# jha_ssr.net
KiCad netlist of a schematic drawn in EAGLE
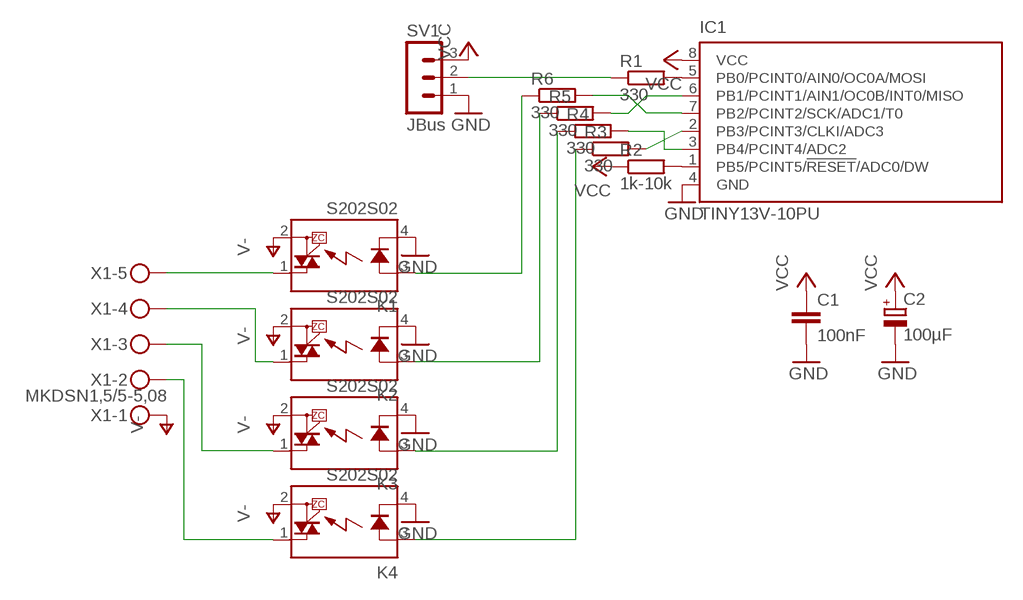
[diagram p0: schematic, sheet 1]

(export (version "E")
  (design (tool "Eeschema 10.0.6"))
  (components
    (comp (ref "C1")
      (value "100nF")
      (footprint "eagle-import:C0603")
      (libsource (lib "eagle-import") (part "C-EUC0603"))
    )
    (comp (ref "C2")
      (value "100µF")
      (footprint "eagle-import:E2,5-5")
      (libsource (lib "eagle-import") (part "CPOL-EUE2.5-5"))
    )
    (comp (ref "IC1")
      (value "TINY13V-10PU")
      (footprint "eagle-import:DIL08")
      (fields
        (field (name "MPN") "ATTINY13V-10PU")
        (field (name "MPN_1") "ATTINY13V-10PU")
        (field (name "OC_FARNELL") "9171576")
        (field (name "OC_NEWARK") "96K6523")
      )
      (libsource (lib "eagle-import") (part "TINY13PUV-10"))
    )
    (comp (ref "K1")
      (value "S202S02")
      (footprint "eagle-import:S202S02")
      (fields (field (name "MPN") "S202S02F"))
      (libsource (lib "eagle-import") (part "S02S022"))
    )
    (comp (ref "K2")
      (value "S202S02")
      (footprint "eagle-import:S202S02")
      (fields (field (name "MPN") "S202S02F"))
      (libsource (lib "eagle-import") (part "S02S022"))
    )
    (comp (ref "K3")
      (value "S202S02")
      (footprint "eagle-import:S202S02")
      (fields (field (name "MPN") "S202S02F"))
      (libsource (lib "eagle-import") (part "S02S022"))
    )
    (comp (ref "K4")
      (value "S202S02")
      (footprint "eagle-import:S202S02")
      (fields (field (name "MPN") "S202S02F"))
      (libsource (lib "eagle-import") (part "S02S022"))
    )
    (comp (ref "R1")
      (value "330")
      (footprint "eagle-import:R0805")
      (libsource (lib "eagle-import") (part "R-EU_R0805"))
    )
    (comp (ref "R2")
      (value "1k-10k")
      (footprint "eagle-import:R0805")
      (libsource (lib "eagle-import") (part "R-EU_R0805"))
    )
    (comp (ref "R3")
      (value "330")
      (footprint "eagle-import:R0805")
      (libsource (lib "eagle-import") (part "R-EU_R0805"))
    )
    (comp (ref "R4")
      (value "330")
      (footprint "eagle-import:R0805")
      (libsource (lib "eagle-import") (part "R-EU_R0805"))
    )
    (comp (ref "R5")
      (value "330")
      (footprint "eagle-import:R0805")
      (libsource (lib "eagle-import") (part "R-EU_R0805"))
    )
    (comp (ref "R6")
      (value "330")
      (footprint "eagle-import:R0805")
      (libsource (lib "eagle-import") (part "R-EU_R0805"))
    )
    (comp (ref "SV1")
      (value "JBus")
      (footprint "eagle-import:MA03-1")
      (libsource (lib "eagle-import") (part "MA03-1"))
    )
    (comp (ref "X1")
      (value "MKDSN1,5/5-5,08")
      (footprint "eagle-import:MKDSN1,5_5-5,08")
      (fields (field (name "MPN") "SMKDSN1,5/5-5,08"))
      (libsource (lib "eagle-import") (part "MKDSN1,5/5-5,08"))
    )
  )
  (nets
    (net (code "1") (name "GND") (class "Default")
      (node (ref "C1") (pin "2") (pinfunction "2_2") (pintype "passive"))
      (node (ref "C2") (pin "-") (pinfunction "-_-") (pintype "passive"))
      (node (ref "IC1") (pin "4") (pinfunction "GND_4") (pintype "power_in"))
      (node (ref "K1") (pin "4") (pinfunction "K_4") (pintype "passive"))
      (node (ref "K2") (pin "4") (pinfunction "K_4") (pintype "passive"))
      (node (ref "K3") (pin "4") (pinfunction "K_4") (pintype "passive"))
      (node (ref "K4") (pin "4") (pinfunction "K_4") (pintype "passive"))
      (node (ref "SV1") (pin "1") (pinfunction "1_1") (pintype "passive"))
    )
    (net (code "2") (name "Net-(IC1-PB0{slash}PCINT0{slash}AIN0{slash}OC0A{slash}MOSI)") (class "Default")
      (node (ref "IC1") (pin "5") (pinfunction "PB0/PCINT0/AIN0/OC0A/MOSI_5") (pintype "bidirectional"))
      (node (ref "R1") (pin "2") (pinfunction "2_2") (pintype "passive"))
    )
    (net (code "3") (name "Net-(IC1-PB1{slash}PCINT1{slash}AIN1{slash}OC0B{slash}INT0{slash}MISO)") (class "Default")
      (node (ref "IC1") (pin "6") (pinfunction "PB1/PCINT1/AIN1/OC0B/INT0/MISO_6") (pintype "bidirectional"))
      (node (ref "R5") (pin "2") (pinfunction "2_2") (pintype "passive"))
    )
    (net (code "4") (name "Net-(IC1-PB2{slash}PCINT2{slash}SCK{slash}ADC1{slash}T0)") (class "Default")
      (node (ref "IC1") (pin "7") (pinfunction "PB2/PCINT2/SCK/ADC1/T0_7") (pintype "bidirectional"))
      (node (ref "R6") (pin "2") (pinfunction "2_2") (pintype "passive"))
    )
    (net (code "5") (name "Net-(IC1-PB3{slash}PCINT3{slash}CLKI{slash}ADC3)") (class "Default")
      (node (ref "IC1") (pin "2") (pinfunction "PB3/PCINT3/CLKI/ADC3_2") (pintype "bidirectional"))
      (node (ref "R3") (pin "2") (pinfunction "2_2") (pintype "passive"))
    )
    (net (code "6") (name "Net-(IC1-PB4{slash}PCINT4{slash}ADC2)") (class "Default")
      (node (ref "IC1") (pin "3") (pinfunction "PB4/PCINT4/ADC2_3") (pintype "bidirectional"))
      (node (ref "R4") (pin "2") (pinfunction "2_2") (pintype "passive"))
    )
    (net (code "7") (name "Net-(IC1-PB5{slash}PCINT5{slash}~{RESET}{slash}ADC0{slash}DW)") (class "Default")
      (node (ref "IC1") (pin "1") (pinfunction "PB5/PCINT5/~{RESET}/ADC0/DW_1") (pintype "bidirectional"))
      (node (ref "R2") (pin "2") (pinfunction "2_2") (pintype "passive"))
    )
    (net (code "8") (name "Net-(K1-A)") (class "Default")
      (node (ref "K1") (pin "3") (pinfunction "A_3") (pintype "passive"))
      (node (ref "R6") (pin "1") (pinfunction "1_1") (pintype "passive"))
    )
    (net (code "9") (name "Net-(K1-DS1)") (class "Default")
      (node (ref "K1") (pin "1") (pinfunction "DS1_1") (pintype "passive"))
      (node (ref "X1") (pin "5") (pinfunction "KL_5") (pintype "passive"))
    )
    (net (code "10") (name "Net-(K2-A)") (class "Default")
      (node (ref "K2") (pin "3") (pinfunction "A_3") (pintype "passive"))
      (node (ref "R5") (pin "1") (pinfunction "1_1") (pintype "passive"))
    )
    (net (code "11") (name "Net-(K2-DS1)") (class "Default")
      (node (ref "K2") (pin "1") (pinfunction "DS1_1") (pintype "passive"))
      (node (ref "X1") (pin "4") (pinfunction "KL_4") (pintype "passive"))
    )
    (net (code "12") (name "Net-(K3-A)") (class "Default")
      (node (ref "K3") (pin "3") (pinfunction "A_3") (pintype "passive"))
      (node (ref "R4") (pin "1") (pinfunction "1_1") (pintype "passive"))
    )
    (net (code "13") (name "Net-(K3-DS1)") (class "Default")
      (node (ref "K3") (pin "1") (pinfunction "DS1_1") (pintype "passive"))
      (node (ref "X1") (pin "3") (pinfunction "KL_3") (pintype "passive"))
    )
    (net (code "14") (name "Net-(K4-A)") (class "Default")
      (node (ref "K4") (pin "3") (pinfunction "A_3") (pintype "passive"))
      (node (ref "R3") (pin "1") (pinfunction "1_1") (pintype "passive"))
    )
    (net (code "15") (name "Net-(K4-DS1)") (class "Default")
      (node (ref "K4") (pin "1") (pinfunction "DS1_1") (pintype "passive"))
      (node (ref "X1") (pin "2") (pinfunction "KL_2") (pintype "passive"))
    )
    (net (code "16") (name "Net-(R1-Pad1)") (class "Default")
      (node (ref "R1") (pin "1") (pinfunction "1_1") (pintype "passive"))
      (node (ref "SV1") (pin "2") (pinfunction "2_2") (pintype "passive"))
    )
    (net (code "17") (name "V-") (class "Default")
      (node (ref "K1") (pin "2") (pinfunction "DS2_2") (pintype "passive"))
      (node (ref "K2") (pin "2") (pinfunction "DS2_2") (pintype "passive"))
      (node (ref "K3") (pin "2") (pinfunction "DS2_2") (pintype "passive"))
      (node (ref "K4") (pin "2") (pinfunction "DS2_2") (pintype "passive"))
      (node (ref "X1") (pin "1") (pinfunction "KL_1") (pintype "passive"))
    )
    (net (code "18") (name "VCC") (class "Default")
      (node (ref "C1") (pin "1") (pinfunction "1_1") (pintype "passive"))
      (node (ref "C2") (pin "+") (pinfunction "+_+") (pintype "passive"))
      (node (ref "IC1") (pin "8") (pinfunction "VCC_8") (pintype "power_in"))
      (node (ref "R2") (pin "1") (pinfunction "1_1") (pintype "passive"))
      (node (ref "SV1") (pin "3") (pinfunction "3_3") (pintype "passive"))
    )
  )
)
